# cs301_YourGroupNumber---------------.net
KiCad netlist of a schematic drawn in Altium Designer
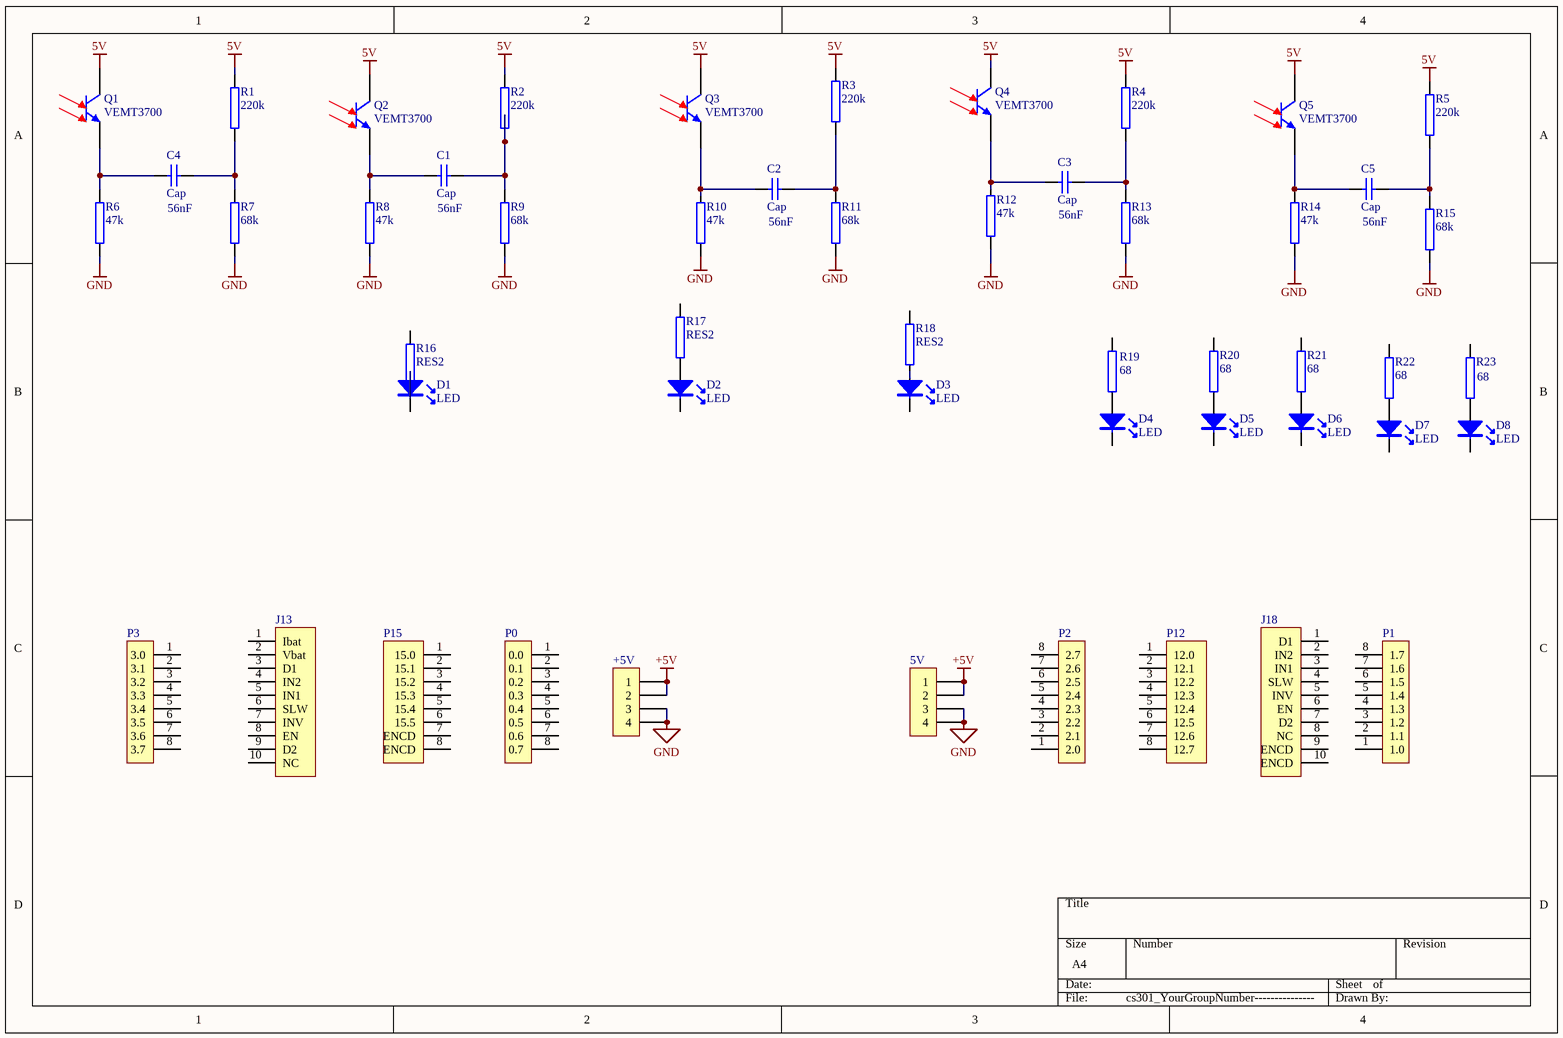
[diagram p0: cs301_YourGroupNumber---------------.SchDoc]

(export (version "E")
  (design (tool "Eeschema 10.0.6"))
  (components
    (comp (ref "+5V")
      (value "5V")
      (footprint "IDC4")
      (description "Connector")
      (libsource (lib "Miscellaneous Devices") (part "CON4"))
    )
    (comp (ref "5V")
      (value "5V")
      (footprint "IDC4")
      (description "Connector")
      (libsource (lib "Miscellaneous Devices") (part "CON4"))
    )
    (comp (ref "C1")
      (value "Cap")
      (footprint "RAD-0.3")
      (description "Capacitor")
      (fields (field (name "ALTIUM_VALUE") "56nF") (field (name "PUBLISHER") "Altium Limited"))
      (libsource (lib "Miscellaneous Devices") (part "Cap"))
    )
    (comp (ref "C2")
      (value "Cap")
      (footprint "RAD-0.3")
      (description "Capacitor")
      (fields (field (name "ALTIUM_VALUE") "56nF") (field (name "PUBLISHER") "Altium Limited"))
      (libsource (lib "Miscellaneous Devices") (part "Cap"))
    )
    (comp (ref "C3")
      (value "Cap")
      (footprint "RAD-0.3")
      (description "Capacitor")
      (fields (field (name "ALTIUM_VALUE") "56nF") (field (name "PUBLISHER") "Altium Limited"))
      (libsource (lib "Miscellaneous Devices") (part "Cap"))
    )
    (comp (ref "C4")
      (value "Cap")
      (footprint "RAD-0.3")
      (description "Capacitor")
      (fields (field (name "ALTIUM_VALUE") "56nF") (field (name "PUBLISHER") "Altium Limited"))
      (libsource (lib "Miscellaneous Devices") (part "Cap"))
    )
    (comp (ref "C5")
      (value "Cap")
      (footprint "RAD-0.3")
      (description "Capacitor")
      (fields (field (name "ALTIUM_VALUE") "56nF") (field (name "PUBLISHER") "Altium Limited"))
      (libsource (lib "Miscellaneous Devices") (part "Cap"))
    )
    (comp (ref "D1") (value "LED") (footprint "LED0.1/5MM") (libsource (lib "COMSYS301_2013") (part "LED")))
    (comp (ref "D2") (value "LED") (footprint "LED0.1/5MM") (libsource (lib "COMSYS301_2013") (part "LED")))
    (comp (ref "D3") (value "LED") (footprint "LED0.1/5MM") (libsource (lib "COMSYS301_2013") (part "LED")))
    (comp (ref "D4") (value "LED") (footprint "LED0.1/5MM") (libsource (lib "COMSYS301_2013") (part "LED")))
    (comp (ref "D5") (value "LED") (footprint "LED0.1/5MM") (libsource (lib "COMSYS301_2013") (part "LED")))
    (comp (ref "D6") (value "LED") (footprint "LED0.1/5MM") (libsource (lib "COMSYS301_2013") (part "LED")))
    (comp (ref "D7") (value "LED") (footprint "LED0.1/5MM") (libsource (lib "COMSYS301_2013") (part "LED")))
    (comp (ref "D8") (value "LED") (footprint "LED0.1/5MM") (libsource (lib "COMSYS301_2013") (part "LED")))
    (comp (ref "J13")
      (value "CON10")
      (footprint "idc10")
      (description "Connector")
      (libsource (lib "Miscellaneous Devices") (part "CON10"))
    )
    (comp (ref "J18")
      (value "CON10")
      (footprint "IDC10")
      (description "Connector")
      (libsource (lib "") (part "CON10_1"))
    )
    (comp (ref "P0")
      (value "P0")
      (footprint "idc8")
      (description "Connector")
      (libsource (lib "Miscellaneous Devices") (part "CON8"))
    )
    (comp (ref "P1")
      (value "P1")
      (footprint "idc8")
      (description "Connector")
      (libsource (lib "") (part "CON8_1"))
    )
    (comp (ref "P2")
      (value "P2")
      (footprint "idc8")
      (description "Connector")
      (libsource (lib "") (part "CON8_2"))
    )
    (comp (ref "P3")
      (value "P3")
      (footprint "idc8")
      (description "Connector")
      (libsource (lib "Miscellaneous Devices") (part "CON8"))
    )
    (comp (ref "P12")
      (value "P12")
      (footprint "idc8")
      (description "Connector")
      (libsource (lib "") (part "CON8_1_1"))
    )
    (comp (ref "P15")
      (value "P15")
      (footprint "idc8")
      (description "Connector")
      (libsource (lib "Miscellaneous Devices") (part "CON8_1"))
    )
    (comp (ref "Q1")
      (value "VEMT3700")
      (footprint "VEMT3700")
      (description "Silicon NPN Phototransistor")
      (libsource (lib "COMSYS301_2013") (part "VEMT3700"))
    )
    (comp (ref "Q2")
      (value "VEMT3700")
      (footprint "VEMT3700")
      (description "Silicon NPN Phototransistor")
      (libsource (lib "COMSYS301_2013") (part "VEMT3700"))
    )
    (comp (ref "Q3")
      (value "VEMT3700")
      (footprint "VEMT3700")
      (description "Silicon NPN Phototransistor")
      (libsource (lib "COMSYS301_2013") (part "VEMT3700"))
    )
    (comp (ref "Q4")
      (value "VEMT3700")
      (footprint "VEMT3700")
      (description "Silicon NPN Phototransistor")
      (libsource (lib "COMSYS301_2013") (part "VEMT3700"))
    )
    (comp (ref "Q5")
      (value "VEMT3700")
      (footprint "VEMT3700")
      (description "Silicon NPN Phototransistor")
      (libsource (lib "COMSYS301_2013") (part "VEMT3700"))
    )
    (comp (ref "R1") (value "220k") (footprint "AXIAL0.4") (libsource (lib "COMSYS301_2013") (part "RES2")))
    (comp (ref "R2") (value "220k") (footprint "AXIAL0.4") (libsource (lib "COMSYS301_2013") (part "RES2")))
    (comp (ref "R3") (value "220k") (footprint "AXIAL0.4") (libsource (lib "COMSYS301_2013") (part "RES2")))
    (comp (ref "R4") (value "220k") (footprint "AXIAL0.4") (libsource (lib "COMSYS301_2013") (part "RES2")))
    (comp (ref "R5") (value "220k") (footprint "AXIAL0.4") (libsource (lib "COMSYS301_2013") (part "RES2")))
    (comp (ref "R6") (value "47k") (footprint "AXIAL0.4") (libsource (lib "COMSYS301_2013") (part "RES2")))
    (comp (ref "R7") (value "68k") (footprint "AXIAL0.4") (libsource (lib "COMSYS301_2013") (part "RES2")))
    (comp (ref "R8") (value "47k") (footprint "AXIAL0.4") (libsource (lib "COMSYS301_2013") (part "RES2")))
    (comp (ref "R9") (value "68k") (footprint "AXIAL0.4") (libsource (lib "COMSYS301_2013") (part "RES2")))
    (comp (ref "R10") (value "47k") (footprint "AXIAL0.4") (libsource (lib "COMSYS301_2013") (part "RES2")))
    (comp (ref "R11") (value "68k") (footprint "AXIAL0.4") (libsource (lib "COMSYS301_2013") (part "RES2")))
    (comp (ref "R12") (value "47k") (footprint "AXIAL0.4") (libsource (lib "COMSYS301_2013") (part "RES2")))
    (comp (ref "R13") (value "68k") (footprint "AXIAL0.4") (libsource (lib "COMSYS301_2013") (part "RES2")))
    (comp (ref "R14") (value "47k") (footprint "AXIAL0.4") (libsource (lib "COMSYS301_2013") (part "RES2")))
    (comp (ref "R15") (value "68k") (footprint "AXIAL0.4") (libsource (lib "COMSYS301_2013") (part "RES2")))
    (comp (ref "R16") (value "RES2") (footprint "AXIAL0.4") (libsource (lib "COMSYS301_2013") (part "RES2")))
    (comp (ref "R17") (value "RES2") (footprint "AXIAL0.4") (libsource (lib "COMSYS301_2013") (part "RES2")))
    (comp (ref "R18") (value "RES2") (footprint "AXIAL0.4") (libsource (lib "COMSYS301_2013") (part "RES2")))
    (comp (ref "R19") (value "68") (footprint "AXIAL0.4") (libsource (lib "COMSYS301_2013") (part "RES2")))
    (comp (ref "R20") (value "68") (footprint "AXIAL0.4") (libsource (lib "COMSYS301_2013") (part "RES2")))
    (comp (ref "R21") (value "68") (footprint "AXIAL0.4") (libsource (lib "COMSYS301_2013") (part "RES2")))
    (comp (ref "R22") (value "68") (footprint "AXIAL0.4") (libsource (lib "COMSYS301_2013") (part "RES2")))
    (comp (ref "R23") (value "68") (footprint "AXIAL0.4") (libsource (lib "COMSYS301_2013") (part "RES2")))
  )
  (nets
    (net (code "1") (name "+5V") (class "Default")
      (node (ref "+5V") (pin "1") (pinfunction "1_1") (pintype "passive"))
      (node (ref "+5V") (pin "2") (pinfunction "2_2") (pintype "passive"))
      (node (ref "5V") (pin "1") (pinfunction "1_1") (pintype "passive"))
      (node (ref "5V") (pin "2") (pinfunction "2_2") (pintype "passive"))
    )
    (net (code "2") (name "5V") (class "Default")
      (node (ref "Q1") (pin "1") (pinfunction "C_1") (pintype "passive"))
      (node (ref "Q2") (pin "1") (pinfunction "C_1") (pintype "passive"))
      (node (ref "Q3") (pin "1") (pinfunction "C_1") (pintype "passive"))
      (node (ref "Q4") (pin "1") (pinfunction "C_1") (pintype "passive"))
      (node (ref "Q5") (pin "1") (pinfunction "C_1") (pintype "passive"))
      (node (ref "R1") (pin "2") (pinfunction "2_2") (pintype "passive"))
      (node (ref "R2") (pin "2") (pinfunction "2_2") (pintype "passive"))
      (node (ref "R3") (pin "2") (pinfunction "2_2") (pintype "passive"))
      (node (ref "R4") (pin "2") (pinfunction "2_2") (pintype "passive"))
      (node (ref "R5") (pin "2") (pinfunction "2_2") (pintype "passive"))
    )
    (net (code "3") (name "GND") (class "Default")
      (node (ref "+5V") (pin "3") (pinfunction "3_3") (pintype "passive"))
      (node (ref "+5V") (pin "4") (pinfunction "4_4") (pintype "passive"))
      (node (ref "5V") (pin "3") (pinfunction "3_3") (pintype "passive"))
      (node (ref "5V") (pin "4") (pinfunction "4_4") (pintype "passive"))
      (node (ref "R10") (pin "1") (pinfunction "1_1") (pintype "passive"))
      (node (ref "R11") (pin "1") (pinfunction "1_1") (pintype "passive"))
      (node (ref "R12") (pin "1") (pinfunction "1_1") (pintype "passive"))
      (node (ref "R13") (pin "1") (pinfunction "1_1") (pintype "passive"))
      (node (ref "R14") (pin "1") (pinfunction "1_1") (pintype "passive"))
      (node (ref "R15") (pin "1") (pinfunction "1_1") (pintype "passive"))
      (node (ref "R6") (pin "1") (pinfunction "1_1") (pintype "passive"))
      (node (ref "R7") (pin "1") (pinfunction "1_1") (pintype "passive"))
      (node (ref "R8") (pin "1") (pinfunction "1_1") (pintype "passive"))
      (node (ref "R9") (pin "1") (pinfunction "1_1") (pintype "passive"))
    )
    (net (code "4") (name "Net-(C1-Pad2)") (class "Default")
      (node (ref "C1") (pin "2") (pinfunction "2_2") (pintype "passive"))
      (node (ref "R2") (pin "1") (pinfunction "1_1") (pintype "passive"))
      (node (ref "R9") (pin "2") (pinfunction "2_2") (pintype "passive"))
    )
    (net (code "5") (name "Net-(C2-Pad2)") (class "Default")
      (node (ref "C2") (pin "2") (pinfunction "2_2") (pintype "passive"))
      (node (ref "R11") (pin "2") (pinfunction "2_2") (pintype "passive"))
      (node (ref "R3") (pin "1") (pinfunction "1_1") (pintype "passive"))
    )
    (net (code "6") (name "Net-(C3-Pad2)") (class "Default")
      (node (ref "C3") (pin "2") (pinfunction "2_2") (pintype "passive"))
      (node (ref "R13") (pin "2") (pinfunction "2_2") (pintype "passive"))
      (node (ref "R4") (pin "1") (pinfunction "1_1") (pintype "passive"))
    )
    (net (code "7") (name "Net-(C4-Pad2)") (class "Default")
      (node (ref "C4") (pin "2") (pinfunction "2_2") (pintype "passive"))
      (node (ref "R1") (pin "1") (pinfunction "1_1") (pintype "passive"))
      (node (ref "R7") (pin "2") (pinfunction "2_2") (pintype "passive"))
    )
    (net (code "8") (name "Net-(C5-Pad2)") (class "Default")
      (node (ref "C5") (pin "2") (pinfunction "2_2") (pintype "passive"))
      (node (ref "R15") (pin "2") (pinfunction "2_2") (pintype "passive"))
      (node (ref "R5") (pin "1") (pinfunction "1_1") (pintype "passive"))
    )
    (net (code "9") (name "Net-(D1-1)") (class "Default")
      (node (ref "D1") (pin "A") (pinfunction "1_A") (pintype "passive"))
      (node (ref "R16") (pin "1") (pinfunction "1_1") (pintype "passive"))
    )
    (net (code "10") (name "Net-(D2-1)") (class "Default")
      (node (ref "D2") (pin "A") (pinfunction "1_A") (pintype "passive"))
      (node (ref "R17") (pin "1") (pinfunction "1_1") (pintype "passive"))
    )
    (net (code "11") (name "Net-(D3-1)") (class "Default")
      (node (ref "D3") (pin "A") (pinfunction "1_A") (pintype "passive"))
      (node (ref "R18") (pin "2") (pinfunction "2_2") (pintype "passive"))
    )
    (net (code "12") (name "Net-(D4-1)") (class "Default")
      (node (ref "D4") (pin "A") (pinfunction "1_A") (pintype "passive"))
      (node (ref "R19") (pin "1") (pinfunction "1_1") (pintype "passive"))
    )
    (net (code "13") (name "Net-(D5-1)") (class "Default")
      (node (ref "D5") (pin "A") (pinfunction "1_A") (pintype "passive"))
      (node (ref "R20") (pin "1") (pinfunction "1_1") (pintype "passive"))
    )
    (net (code "14") (name "Net-(D6-1)") (class "Default")
      (node (ref "D6") (pin "A") (pinfunction "1_A") (pintype "passive"))
      (node (ref "R21") (pin "1") (pinfunction "1_1") (pintype "passive"))
    )
    (net (code "15") (name "Net-(D7-1)") (class "Default")
      (node (ref "D7") (pin "A") (pinfunction "1_A") (pintype "passive"))
      (node (ref "R22") (pin "1") (pinfunction "1_1") (pintype "passive"))
    )
    (net (code "16") (name "Net-(D8-1)") (class "Default")
      (node (ref "D8") (pin "A") (pinfunction "1_A") (pintype "passive"))
      (node (ref "R23") (pin "1") (pinfunction "1_1") (pintype "passive"))
    )
    (net (code "17") (name "Net-(Q1-E)") (class "Default")
      (node (ref "C4") (pin "1") (pinfunction "1_1") (pintype "passive"))
      (node (ref "Q1") (pin "2") (pinfunction "E_2") (pintype "passive"))
      (node (ref "R6") (pin "2") (pinfunction "2_2") (pintype "passive"))
    )
    (net (code "18") (name "Net-(Q2-E)") (class "Default")
      (node (ref "C1") (pin "1") (pinfunction "1_1") (pintype "passive"))
      (node (ref "Q2") (pin "2") (pinfunction "E_2") (pintype "passive"))
      (node (ref "R8") (pin "2") (pinfunction "2_2") (pintype "passive"))
    )
    (net (code "19") (name "Net-(Q3-E)") (class "Default")
      (node (ref "C2") (pin "1") (pinfunction "1_1") (pintype "passive"))
      (node (ref "Q3") (pin "2") (pinfunction "E_2") (pintype "passive"))
      (node (ref "R10") (pin "2") (pinfunction "2_2") (pintype "passive"))
    )
    (net (code "20") (name "Net-(Q4-E)") (class "Default")
      (node (ref "C3") (pin "1") (pinfunction "1_1") (pintype "passive"))
      (node (ref "Q4") (pin "2") (pinfunction "E_2") (pintype "passive"))
      (node (ref "R12") (pin "2") (pinfunction "2_2") (pintype "passive"))
    )
    (net (code "21") (name "Net-(Q5-E)") (class "Default")
      (node (ref "C5") (pin "1") (pinfunction "1_1") (pintype "passive"))
      (node (ref "Q5") (pin "2") (pinfunction "E_2") (pintype "passive"))
      (node (ref "R14") (pin "2") (pinfunction "2_2") (pintype "passive"))
    )
    (net (code "22") (name "unconnected-(D1-2-PadK)") (class "Default")
      (node (ref "D1") (pin "K") (pinfunction "2_K") (pintype "passive"))
    )
    (net (code "23") (name "unconnected-(D2-2-PadK)") (class "Default")
      (node (ref "D2") (pin "K") (pinfunction "2_K") (pintype "passive"))
    )
    (net (code "24") (name "unconnected-(D3-2-PadK)") (class "Default")
      (node (ref "D3") (pin "K") (pinfunction "2_K") (pintype "passive"))
    )
    (net (code "25") (name "unconnected-(D4-2-PadK)") (class "Default")
      (node (ref "D4") (pin "K") (pinfunction "2_K") (pintype "passive"))
    )
    (net (code "26") (name "unconnected-(D5-2-PadK)") (class "Default")
      (node (ref "D5") (pin "K") (pinfunction "2_K") (pintype "passive"))
    )
    (net (code "27") (name "unconnected-(D6-2-PadK)") (class "Default")
      (node (ref "D6") (pin "K") (pinfunction "2_K") (pintype "passive"))
    )
    (net (code "28") (name "unconnected-(D7-2-PadK)") (class "Default")
      (node (ref "D7") (pin "K") (pinfunction "2_K") (pintype "passive"))
    )
    (net (code "29") (name "unconnected-(D8-2-PadK)") (class "Default")
      (node (ref "D8") (pin "K") (pinfunction "2_K") (pintype "passive"))
    )
    (net (code "30") (name "unconnected-(J13-D1-Pad3)") (class "Default")
      (node (ref "J13") (pin "3") (pinfunction "D1_3") (pintype "passive"))
    )
    (net (code "31") (name "unconnected-(J13-D2-Pad9)") (class "Default")
      (node (ref "J13") (pin "9") (pinfunction "D2_9") (pintype "passive"))
    )
    (net (code "32") (name "unconnected-(J13-EN-Pad8)") (class "Default")
      (node (ref "J13") (pin "8") (pinfunction "EN_8") (pintype "passive"))
    )
    (net (code "33") (name "unconnected-(J13-IN1-Pad5)") (class "Default")
      (node (ref "J13") (pin "5") (pinfunction "IN1_5") (pintype "passive"))
    )
    (net (code "34") (name "unconnected-(J13-IN2-Pad4)") (class "Default")
      (node (ref "J13") (pin "4") (pinfunction "IN2_4") (pintype "passive"))
    )
    (net (code "35") (name "unconnected-(J13-INV-Pad7)") (class "Default")
      (node (ref "J13") (pin "7") (pinfunction "INV_7") (pintype "passive"))
    )
    (net (code "36") (name "unconnected-(J13-Ibat-Pad1)") (class "Default")
      (node (ref "J13") (pin "1") (pinfunction "Ibat_1") (pintype "passive"))
    )
    (net (code "37") (name "unconnected-(J13-NC-Pad10)") (class "Default")
      (node (ref "J13") (pin "10") (pinfunction "NC_10") (pintype "passive"))
    )
    (net (code "38") (name "unconnected-(J13-SLW-Pad6)") (class "Default")
      (node (ref "J13") (pin "6") (pinfunction "SLW_6") (pintype "passive"))
    )
    (net (code "39") (name "unconnected-(J13-Vbat-Pad2)") (class "Default")
      (node (ref "J13") (pin "2") (pinfunction "Vbat_2") (pintype "passive"))
    )
    (net (code "40") (name "unconnected-(J18-D1-Pad1)") (class "Default")
      (node (ref "J18") (pin "1") (pinfunction "D1_1") (pintype "passive"))
    )
    (net (code "41") (name "unconnected-(J18-D2-Pad7)") (class "Default")
      (node (ref "J18") (pin "7") (pinfunction "D2_7") (pintype "passive"))
    )
    (net (code "42") (name "unconnected-(J18-EN-Pad6)") (class "Default")
      (node (ref "J18") (pin "6") (pinfunction "EN_6") (pintype "passive"))
    )
    (net (code "43") (name "unconnected-(J18-ENCD-Pad9)") (class "Default")
      (node (ref "J18") (pin "9") (pinfunction "ENCD_9") (pintype "passive"))
    )
    (net (code "44") (name "unconnected-(J18-ENCD-Pad10)") (class "Default")
      (node (ref "J18") (pin "10") (pinfunction "ENCD_10") (pintype "passive"))
    )
    (net (code "45") (name "unconnected-(J18-IN1-Pad3)") (class "Default")
      (node (ref "J18") (pin "3") (pinfunction "IN1_3") (pintype "passive"))
    )
    (net (code "46") (name "unconnected-(J18-IN2-Pad2)") (class "Default")
      (node (ref "J18") (pin "2") (pinfunction "IN2_2") (pintype "passive"))
    )
    (net (code "47") (name "unconnected-(J18-INV-Pad5)") (class "Default")
      (node (ref "J18") (pin "5") (pinfunction "INV_5") (pintype "passive"))
    )
    (net (code "48") (name "unconnected-(J18-NC-Pad8)") (class "Default")
      (node (ref "J18") (pin "8") (pinfunction "NC_8") (pintype "passive"))
    )
    (net (code "49") (name "unconnected-(J18-SLW-Pad4)") (class "Default")
      (node (ref "J18") (pin "4") (pinfunction "SLW_4") (pintype "passive"))
    )
    (net (code "50") (name "unconnected-(P0-3.0-Pad1)") (class "Default")
      (node (ref "P0") (pin "1") (pinfunction "3.0_1") (pintype "passive"))
    )
    (net (code "51") (name "unconnected-(P0-3.1-Pad2)") (class "Default")
      (node (ref "P0") (pin "2") (pinfunction "3.1_2") (pintype "passive"))
    )
    (net (code "52") (name "unconnected-(P0-3.2-Pad3)") (class "Default")
      (node (ref "P0") (pin "3") (pinfunction "3.2_3") (pintype "passive"))
    )
    (net (code "53") (name "unconnected-(P0-3.3-Pad4)") (class "Default")
      (node (ref "P0") (pin "4") (pinfunction "3.3_4") (pintype "passive"))
    )
    (net (code "54") (name "unconnected-(P0-3.4-Pad5)") (class "Default")
      (node (ref "P0") (pin "5") (pinfunction "3.4_5") (pintype "passive"))
    )
    (net (code "55") (name "unconnected-(P0-3.5-Pad6)") (class "Default")
      (node (ref "P0") (pin "6") (pinfunction "3.5_6") (pintype "passive"))
    )
    (net (code "56") (name "unconnected-(P0-3.6-Pad7)") (class "Default")
      (node (ref "P0") (pin "7") (pinfunction "3.6_7") (pintype "passive"))
    )
    (net (code "57") (name "unconnected-(P0-3.7-Pad8)") (class "Default")
      (node (ref "P0") (pin "8") (pinfunction "3.7_8") (pintype "passive"))
    )
    (net (code "58") (name "unconnected-(P1-1.0-Pad1)") (class "Default")
      (node (ref "P1") (pin "1") (pinfunction "1.0_1") (pintype "passive"))
    )
    (net (code "59") (name "unconnected-(P1-1.1-Pad2)") (class "Default")
      (node (ref "P1") (pin "2") (pinfunction "1.1_2") (pintype "passive"))
    )
    (net (code "60") (name "unconnected-(P1-1.2-Pad3)") (class "Default")
      (node (ref "P1") (pin "3") (pinfunction "1.2_3") (pintype "passive"))
    )
    (net (code "61") (name "unconnected-(P1-1.3-Pad4)") (class "Default")
      (node (ref "P1") (pin "4") (pinfunction "1.3_4") (pintype "passive"))
    )
    (net (code "62") (name "unconnected-(P1-1.4-Pad5)") (class "Default")
      (node (ref "P1") (pin "5") (pinfunction "1.4_5") (pintype "passive"))
    )
    (net (code "63") (name "unconnected-(P1-1.5-Pad6)") (class "Default")
      (node (ref "P1") (pin "6") (pinfunction "1.5_6") (pintype "passive"))
    )
    (net (code "64") (name "unconnected-(P1-1.6-Pad7)") (class "Default")
      (node (ref "P1") (pin "7") (pinfunction "1.6_7") (pintype "passive"))
    )
    (net (code "65") (name "unconnected-(P1-1.7-Pad8)") (class "Default")
      (node (ref "P1") (pin "8") (pinfunction "1.7_8") (pintype "passive"))
    )
    (net (code "66") (name "unconnected-(P2-2.0-Pad1)") (class "Default")
      (node (ref "P2") (pin "1") (pinfunction "2.0_1") (pintype "passive"))
    )
    (net (code "67") (name "unconnected-(P2-2.1-Pad2)") (class "Default")
      (node (ref "P2") (pin "2") (pinfunction "2.1_2") (pintype "passive"))
    )
    (net (code "68") (name "unconnected-(P2-2.2-Pad3)") (class "Default")
      (node (ref "P2") (pin "3") (pinfunction "2.2_3") (pintype "passive"))
    )
    (net (code "69") (name "unconnected-(P2-2.3-Pad4)") (class "Default")
      (node (ref "P2") (pin "4") (pinfunction "2.3_4") (pintype "passive"))
    )
    (net (code "70") (name "unconnected-(P2-2.4-Pad5)") (class "Default")
      (node (ref "P2") (pin "5") (pinfunction "2.4_5") (pintype "passive"))
    )
    (net (code "71") (name "unconnected-(P2-2.5-Pad6)") (class "Default")
      (node (ref "P2") (pin "6") (pinfunction "2.5_6") (pintype "passive"))
    )
    (net (code "72") (name "unconnected-(P2-2.6-Pad7)") (class "Default")
      (node (ref "P2") (pin "7") (pinfunction "2.6_7") (pintype "passive"))
    )
    (net (code "73") (name "unconnected-(P2-2.7-Pad8)") (class "Default")
      (node (ref "P2") (pin "8") (pinfunction "2.7_8") (pintype "passive"))
    )
    (net (code "74") (name "unconnected-(P3-3.0-Pad1)") (class "Default")
      (node (ref "P3") (pin "1") (pinfunction "3.0_1") (pintype "passive"))
    )
    (net (code "75") (name "unconnected-(P3-3.1-Pad2)") (class "Default")
      (node (ref "P3") (pin "2") (pinfunction "3.1_2") (pintype "passive"))
    )
    (net (code "76") (name "unconnected-(P3-3.2-Pad3)") (class "Default")
      (node (ref "P3") (pin "3") (pinfunction "3.2_3") (pintype "passive"))
    )
    (net (code "77") (name "unconnected-(P3-3.3-Pad4)") (class "Default")
      (node (ref "P3") (pin "4") (pinfunction "3.3_4") (pintype "passive"))
    )
    (net (code "78") (name "unconnected-(P3-3.4-Pad5)") (class "Default")
      (node (ref "P3") (pin "5") (pinfunction "3.4_5") (pintype "passive"))
    )
    (net (code "79") (name "unconnected-(P3-3.5-Pad6)") (class "Default")
      (node (ref "P3") (pin "6") (pinfunction "3.5_6") (pintype "passive"))
    )
    (net (code "80") (name "unconnected-(P3-3.6-Pad7)") (class "Default")
      (node (ref "P3") (pin "7") (pinfunction "3.6_7") (pintype "passive"))
    )
    (net (code "81") (name "unconnected-(P3-3.7-Pad8)") (class "Default")
      (node (ref "P3") (pin "8") (pinfunction "3.7_8") (pintype "passive"))
    )
    (net (code "82") (name "unconnected-(P12-12.0-Pad1)") (class "Default")
      (node (ref "P12") (pin "1") (pinfunction "12.0_1") (pintype "passive"))
    )
    (net (code "83") (name "unconnected-(P12-12.1-Pad2)") (class "Default")
      (node (ref "P12") (pin "2") (pinfunction "12.1_2") (pintype "passive"))
    )
    (net (code "84") (name "unconnected-(P12-12.2-Pad3)") (class "Default")
      (node (ref "P12") (pin "3") (pinfunction "12.2_3") (pintype "passive"))
    )
    (net (code "85") (name "unconnected-(P12-12.3-Pad4)") (class "Default")
      (node (ref "P12") (pin "4") (pinfunction "12.3_4") (pintype "passive"))
    )
    (net (code "86") (name "unconnected-(P12-12.4-Pad5)") (class "Default")
      (node (ref "P12") (pin "5") (pinfunction "12.4_5") (pintype "passive"))
    )
    (net (code "87") (name "unconnected-(P12-12.5-Pad6)") (class "Default")
      (node (ref "P12") (pin "6") (pinfunction "12.5_6") (pintype "passive"))
    )
    (net (code "88") (name "unconnected-(P12-12.6-Pad7)") (class "Default")
      (node (ref "P12") (pin "7") (pinfunction "12.6_7") (pintype "passive"))
    )
    (net (code "89") (name "unconnected-(P12-12.7-Pad8)") (class "Default")
      (node (ref "P12") (pin "8") (pinfunction "12.7_8") (pintype "passive"))
    )
    (net (code "90") (name "unconnected-(P15-15.0-Pad1)") (class "Default")
      (node (ref "P15") (pin "1") (pinfunction "15.0_1") (pintype "passive"))
    )
    (net (code "91") (name "unconnected-(P15-15.1-Pad2)") (class "Default")
      (node (ref "P15") (pin "2") (pinfunction "15.1_2") (pintype "passive"))
    )
    (net (code "92") (name "unconnected-(P15-15.2-Pad3)") (class "Default")
      (node (ref "P15") (pin "3") (pinfunction "15.2_3") (pintype "passive"))
    )
    (net (code "93") (name "unconnected-(P15-15.3-Pad4)") (class "Default")
      (node (ref "P15") (pin "4") (pinfunction "15.3_4") (pintype "passive"))
    )
    (net (code "94") (name "unconnected-(P15-15.4-Pad5)") (class "Default")
      (node (ref "P15") (pin "5") (pinfunction "15.4_5") (pintype "passive"))
    )
    (net (code "95") (name "unconnected-(P15-15.5-Pad6)") (class "Default")
      (node (ref "P15") (pin "6") (pinfunction "15.5_6") (pintype "passive"))
    )
    (net (code "96") (name "unconnected-(P15-ENCD-Pad7)") (class "Default")
      (node (ref "P15") (pin "7") (pinfunction "ENCD_7") (pintype "passive"))
    )
    (net (code "97") (name "unconnected-(P15-ENCD-Pad8)") (class "Default")
      (node (ref "P15") (pin "8") (pinfunction "ENCD_8") (pintype "passive"))
    )
    (net (code "98") (name "unconnected-(R16-Pad2)") (class "Default")
      (node (ref "R16") (pin "2") (pinfunction "2_2") (pintype "passive"))
    )
    (net (code "99") (name "unconnected-(R17-Pad2)") (class "Default")
      (node (ref "R17") (pin "2") (pinfunction "2_2") (pintype "passive"))
    )
    (net (code "100") (name "unconnected-(R18-Pad1)") (class "Default")
      (node (ref "R18") (pin "1") (pinfunction "1_1") (pintype "passive"))
    )
    (net (code "101") (name "unconnected-(R19-Pad2)") (class "Default")
      (node (ref "R19") (pin "2") (pinfunction "2_2") (pintype "passive"))
    )
    (net (code "102") (name "unconnected-(R20-Pad2)") (class "Default")
      (node (ref "R20") (pin "2") (pinfunction "2_2") (pintype "passive"))
    )
    (net (code "103") (name "unconnected-(R21-Pad2)") (class "Default")
      (node (ref "R21") (pin "2") (pinfunction "2_2") (pintype "passive"))
    )
    (net (code "104") (name "unconnected-(R22-Pad2)") (class "Default")
      (node (ref "R22") (pin "2") (pinfunction "2_2") (pintype "passive"))
    )
    (net (code "105") (name "unconnected-(R23-Pad2)") (class "Default")
      (node (ref "R23") (pin "2") (pinfunction "2_2") (pintype "passive"))
    )
  )
)
